# Main_SCH.net
KiCad netlist of a schematic drawn in Altium Designer
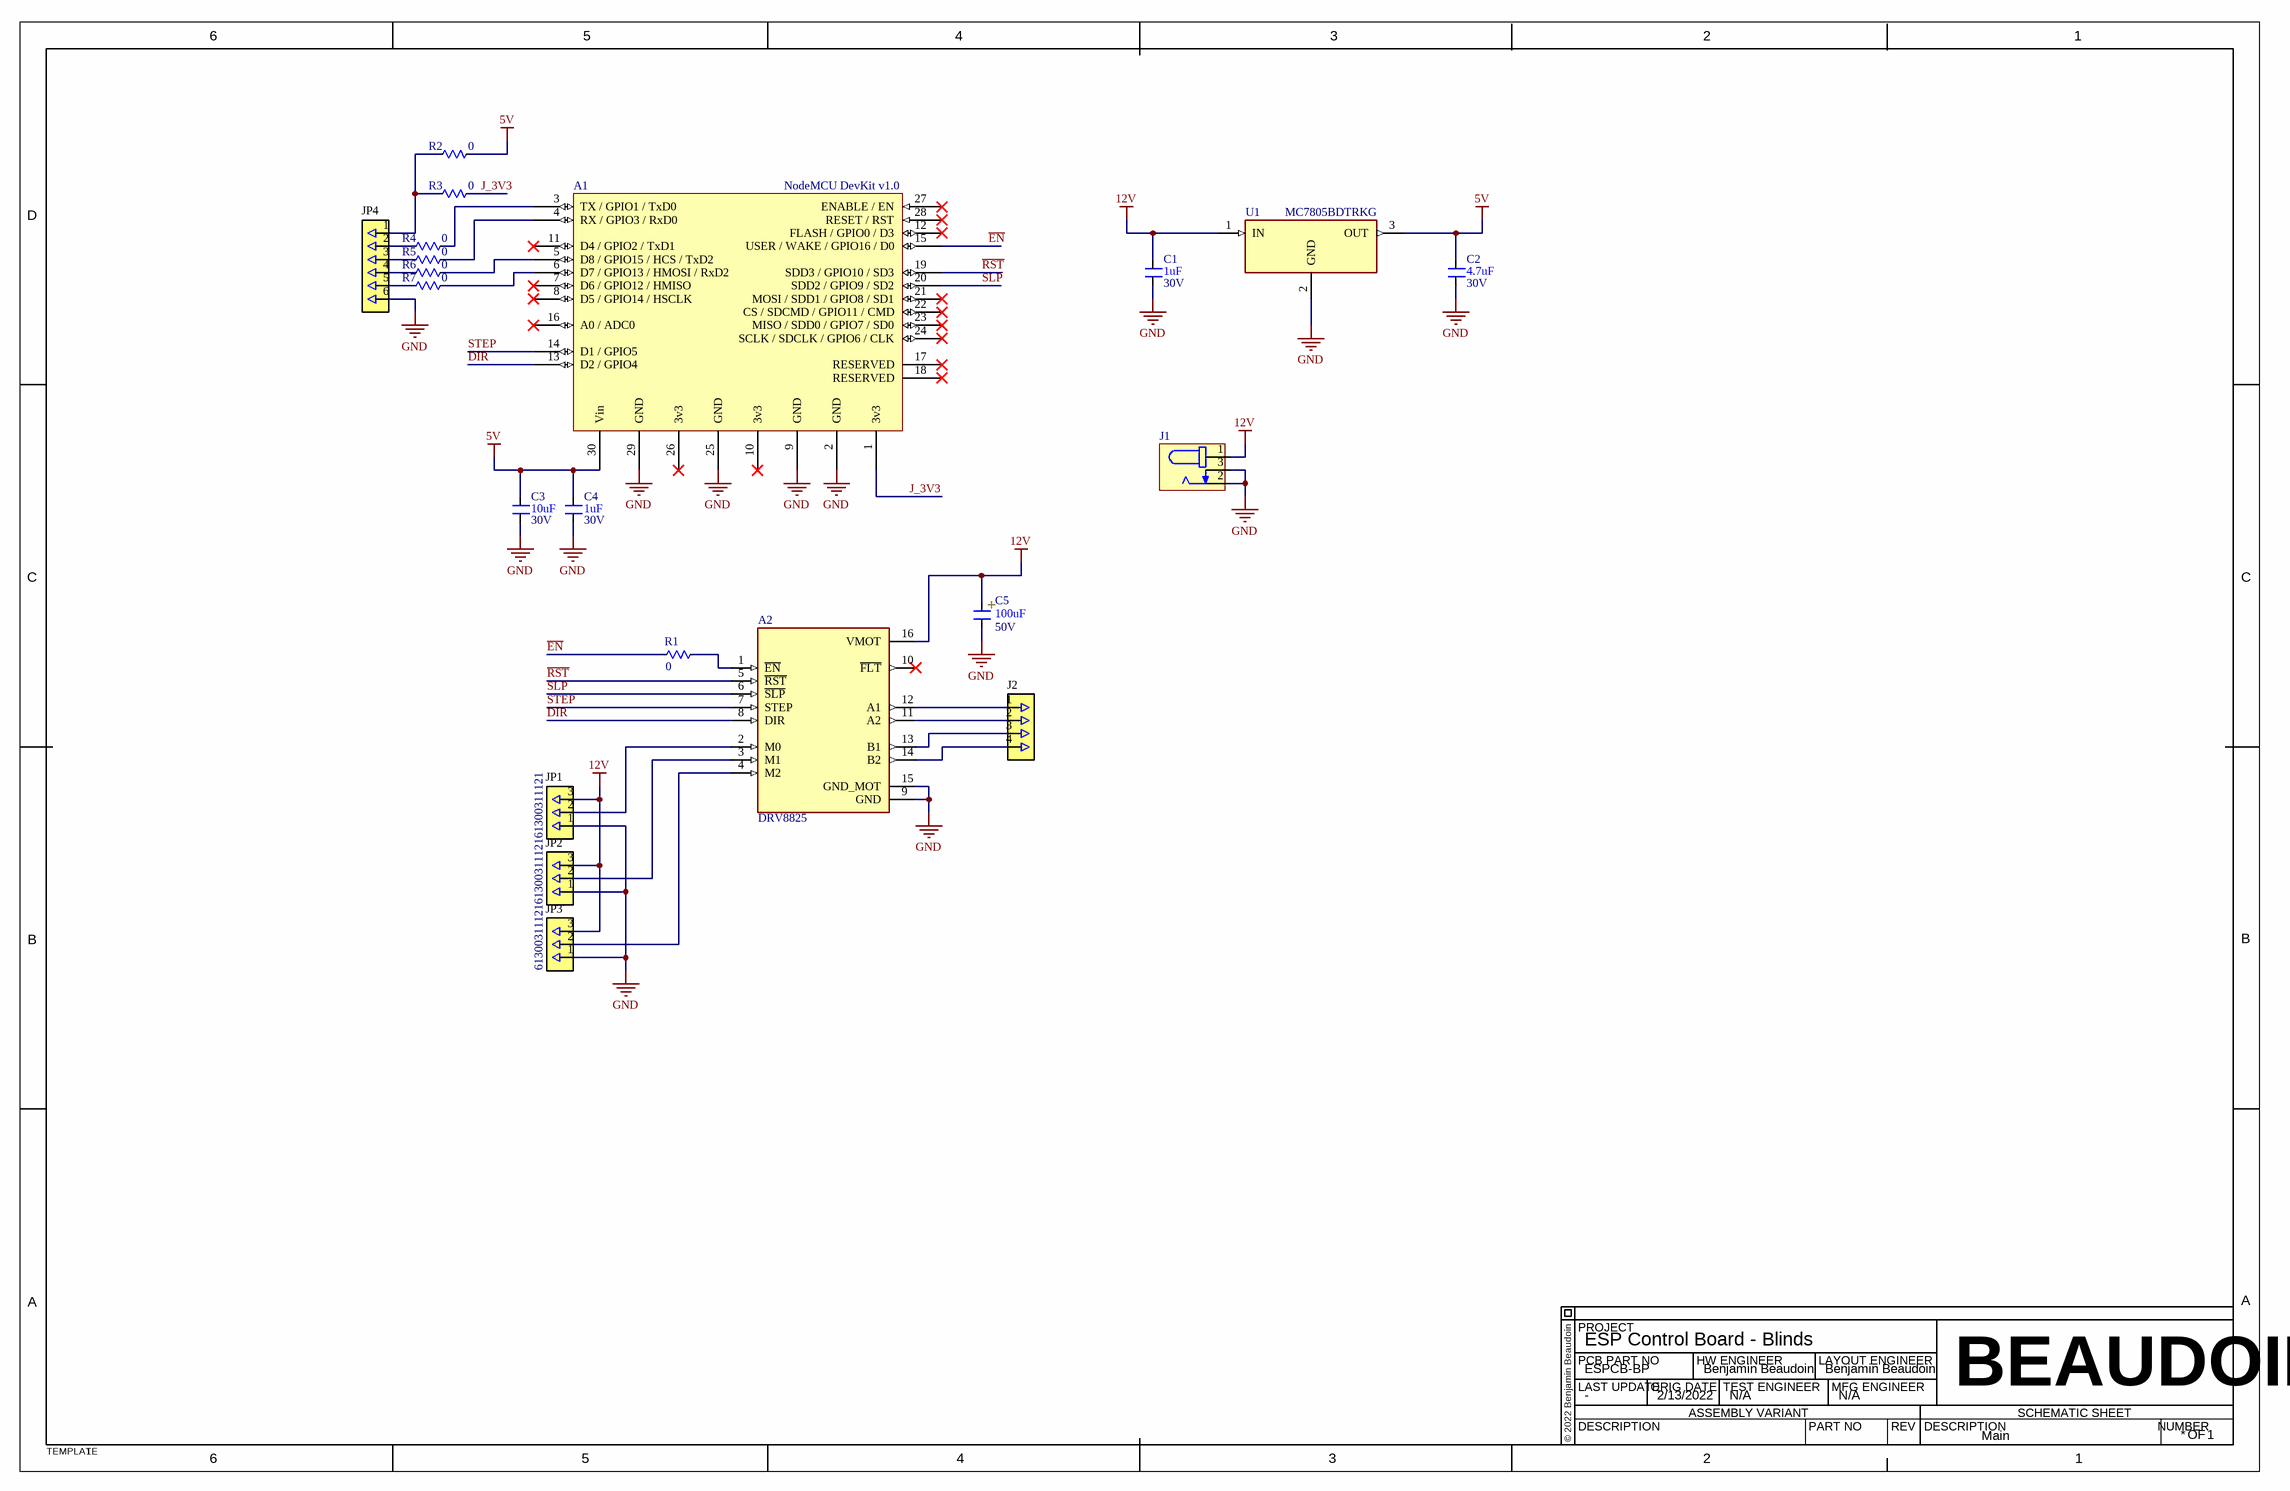
[diagram p0: Main_SCH.SchDoc]

(export (version "E")
  (design (tool "Eeschema 10.0.6"))
  (components
    (comp (ref "A1")
      (value "NodeMCU DevKit v1.0")
      (footprint "NodeMCU DevKit v1.0 - No Labels")
      (libsource (lib "Motorized_Blinds_IntLib") (part "NodeMCU DevKit v1.0"))
    )
    (comp (ref "A2")
      (value "DRV8825")
      (footprint "IC_DRV8825_STEPPER_MOTOR_DRIVER_CARRIER")
      (description "DRV8825 Motor Controller/Driver Power Management Evaluation Board")
      (fields (field (name "MANUFACTURER") "Pololu"))
      (libsource (lib "Motorized_Blinds_IntLib") (part "DRV8825_STEPPER_MOTOR_DRIVER_CARRIER"))
    )
    (comp (ref "C1")
      (value "1uF")
      (footprint "C0603")
      (description "SMCAP NoPol")
      (fields (field (name "VMAX") "30V"))
      (libsource (lib "Motorized_Blinds_IntLib") (part "CAP-NoPol"))
    )
    (comp (ref "C2")
      (value "4.7uF")
      (footprint "C0603")
      (description "SMCAP NoPol")
      (fields (field (name "VMAX") "30V"))
      (libsource (lib "Motorized_Blinds_IntLib") (part "CAP-NoPol"))
    )
    (comp (ref "C3")
      (value "10uF")
      (footprint "C0805")
      (description "SMCAP NoPol")
      (fields (field (name "VMAX") "30V"))
      (libsource (lib "Motorized_Blinds_IntLib") (part "CAP-NoPol"))
    )
    (comp (ref "C4")
      (value "1uF")
      (footprint "C0603")
      (description "SMCAP NoPol")
      (fields (field (name "VMAX") "30V"))
      (libsource (lib "Motorized_Blinds_IntLib") (part "CAP-NoPol"))
    )
    (comp (ref "C5")
      (value "100uF")
      (footprint "CAPAE1050X1050N")
      (description "CAP ALUM 100UF 20% 50V SMD")
      (fields (field (name "MANUFACTURER") "Vishay") (field (name "VMAX") "50V"))
      (libsource (lib "Motorized_Blinds_IntLib") (part "CAP-Pol_MAL214699103E3"))
    )
    (comp (ref "J1")
      (value "PJ-036AH-SMT-TR")
      (footprint "CUI_PJ-036AH-SMT-TR")
      (description "2.0 x 6.3 mm, 5.0 A, Horizontal, Surface Mount _SMT_, Dc Power Jack Connector")
      (fields (field (name "MANUFACTURER") "CUI Devices"))
      (libsource (lib "Motorized_Blinds_IntLib") (part "PJ-036AH-SMT-TR"))
    )
    (comp (ref "J2")
      (value "~")
      (footprint "JP_J4_2.54mm")
      (description "CONN HEADER VERT 4POS 2.54MM")
      (libsource (lib "Motorized_Blinds_IntLib") (part "JP_J4_2.54mm"))
    )
    (comp (ref "JP1")
      (value "61300311121")
      (footprint "JP_61300311121")
      (description "CONN HEADER VERT 3POS 2.54MM")
      (libsource (lib "Motorized_Blinds_IntLib") (part "JP_61300311121"))
    )
    (comp (ref "JP2")
      (value "61300311121")
      (footprint "JP_61300311121")
      (description "CONN HEADER VERT 3POS 2.54MM")
      (libsource (lib "Motorized_Blinds_IntLib") (part "JP_61300311121"))
    )
    (comp (ref "JP3")
      (value "61300311121")
      (footprint "JP_61300311121")
      (description "CONN HEADER VERT 3POS 2.54MM")
      (libsource (lib "Motorized_Blinds_IntLib") (part "JP_61300311121"))
    )
    (comp (ref "JP4")
      (value "~")
      (footprint "JP_J6_2.54mm")
      (description "CONN HEADER VERT 6POS 2.54MM")
      (libsource (lib "Motorized_Blinds_IntLib") (part "JP_J6_2.54mm"))
    )
    (comp (ref "R1")
      (value "0")
      (footprint "R0603")
      (description "SMRES")
      (libsource (lib "Motorized_Blinds_IntLib") (part "Res"))
    )
    (comp (ref "R2")
      (value "0")
      (footprint "R0603")
      (description "SMRES")
      (libsource (lib "Motorized_Blinds_IntLib") (part "Res"))
    )
    (comp (ref "R3")
      (value "0")
      (footprint "R0603")
      (description "SMRES")
      (libsource (lib "Motorized_Blinds_IntLib") (part "Res"))
    )
    (comp (ref "R4")
      (value "0")
      (footprint "R0603")
      (description "SMRES")
      (libsource (lib "Motorized_Blinds_IntLib") (part "Res"))
    )
    (comp (ref "R5")
      (value "0")
      (footprint "R0603")
      (description "SMRES")
      (libsource (lib "Motorized_Blinds_IntLib") (part "Res"))
    )
    (comp (ref "R6")
      (value "0")
      (footprint "R0603")
      (description "SMRES")
      (libsource (lib "Motorized_Blinds_IntLib") (part "Res"))
    )
    (comp (ref "R7")
      (value "0")
      (footprint "R0603")
      (description "SMRES")
      (libsource (lib "Motorized_Blinds_IntLib") (part "Res"))
    )
    (comp (ref "U1")
      (value "MC7805BDTRKG")
      (footprint "DPAK229P990X238-4N")
      (description "Linear Voltage Regulator IC 1 Output 1A DPAK")
      (fields (field (name "MANUFACTURER") "ON Semiconductor"))
      (libsource (lib "Motorized_Blinds_IntLib") (part "MC7805BDTRKG"))
    )
  )
  (nets
    (net (code "1") (name "/DIR") (class "Default")
      (node (ref "A1") (pin "13") (pinfunction "D2_/_GPIO4_13") (pintype "bidirectional"))
      (node (ref "A2") (pin "8") (pinfunction "DIR_8") (pintype "input"))
    )
    (net (code "2") (name "/J_3V3") (class "Default")
      (node (ref "A1") (pin "1") (pinfunction "3v3_1") (pintype "power_in"))
      (node (ref "R3") (pin "2") (pintype "passive"))
    )
    (net (code "3") (name "/STEP") (class "Default")
      (node (ref "A1") (pin "14") (pinfunction "D1_/_GPIO5_14") (pintype "bidirectional"))
      (node (ref "A2") (pin "7") (pinfunction "STEP_7") (pintype "input"))
    )
    (net (code "4") (name "/~{EN}") (class "Default")
      (node (ref "A1") (pin "15") (pinfunction "USER_/_WAKE_/_GPIO16_/_D0_15") (pintype "bidirectional"))
      (node (ref "R1") (pin "1") (pintype "passive"))
    )
    (net (code "5") (name "/~{RST}") (class "Default")
      (node (ref "A1") (pin "19") (pinfunction "SDD3_/_GPIO10_/_SD3_19") (pintype "bidirectional"))
      (node (ref "A2") (pin "5") (pinfunction "~{RST}_5") (pintype "input"))
    )
    (net (code "6") (name "/~{SLP}") (class "Default")
      (node (ref "A1") (pin "20") (pinfunction "SDD2_/_GPIO9_/_SD2_20") (pintype "bidirectional"))
      (node (ref "A2") (pin "6") (pinfunction "~{SLP}_6") (pintype "input"))
    )
    (net (code "7") (name "5V") (class "Default")
      (node (ref "A1") (pin "30") (pinfunction "Vin_30") (pintype "passive"))
      (node (ref "C2") (pin "1") (pintype "passive"))
      (node (ref "C3") (pin "1") (pintype "passive"))
      (node (ref "C4") (pin "1") (pintype "passive"))
      (node (ref "R2") (pin "2") (pintype "passive"))
      (node (ref "U1") (pin "3") (pinfunction "OUT_3") (pintype "output"))
    )
    (net (code "8") (name "12V") (class "Default")
      (node (ref "A2") (pin "16") (pinfunction "VMOT_16") (pintype "power_in"))
      (node (ref "C1") (pin "1") (pintype "passive"))
      (node (ref "C5") (pin "1") (pintype "passive"))
      (node (ref "J1") (pin "1") (pinfunction "1_1") (pintype "passive"))
      (node (ref "JP1") (pin "3") (pintype "passive"))
      (node (ref "JP2") (pin "3") (pintype "passive"))
      (node (ref "JP3") (pin "3") (pintype "passive"))
      (node (ref "U1") (pin "1") (pinfunction "IN_1") (pintype "input"))
    )
    (net (code "9") (name "GND") (class "Default")
      (node (ref "A1") (pin "2") (pinfunction "GND_2") (pintype "power_in"))
      (node (ref "A1") (pin "25") (pinfunction "GND_25") (pintype "power_in"))
      (node (ref "A1") (pin "29") (pinfunction "GND_29") (pintype "passive"))
      (node (ref "A1") (pin "9") (pinfunction "GND_9") (pintype "power_in"))
      (node (ref "A2") (pin "15") (pinfunction "GND_MOT_15") (pintype "power_in"))
      (node (ref "A2") (pin "9") (pinfunction "GND_9") (pintype "power_in"))
      (node (ref "C1") (pin "2") (pintype "passive"))
      (node (ref "C2") (pin "2") (pintype "passive"))
      (node (ref "C3") (pin "2") (pintype "passive"))
      (node (ref "C4") (pin "2") (pintype "passive"))
      (node (ref "C5") (pin "2") (pintype "passive"))
      (node (ref "J1") (pin "2") (pinfunction "2_2") (pintype "passive"))
      (node (ref "J1") (pin "3") (pinfunction "3_3") (pintype "passive"))
      (node (ref "JP1") (pin "1") (pintype "passive"))
      (node (ref "JP2") (pin "1") (pintype "passive"))
      (node (ref "JP3") (pin "1") (pintype "passive"))
      (node (ref "JP4") (pin "6") (pintype "passive"))
      (node (ref "U1") (pin "2") (pinfunction "GND_2") (pintype "power_in"))
    )
    (net (code "10") (name "Net-(A1-D7_{slash}_GPIO13_{slash}_HMOSI_{slash}_RxD2)") (class "Default")
      (node (ref "A1") (pin "6") (pinfunction "D7_/_GPIO13_/_HMOSI_/_RxD2_6") (pintype "bidirectional"))
      (node (ref "R7") (pin "2") (pintype "passive"))
    )
    (net (code "11") (name "Net-(A1-D8_{slash}_GPIO15_{slash}_HCS_{slash}_TxD2)") (class "Default")
      (node (ref "A1") (pin "5") (pinfunction "D8_/_GPIO15_/_HCS_/_TxD2_5") (pintype "bidirectional"))
      (node (ref "R6") (pin "2") (pintype "passive"))
    )
    (net (code "12") (name "Net-(A1-RX_{slash}_GPIO3_{slash}_RxD0)") (class "Default")
      (node (ref "A1") (pin "4") (pinfunction "RX_/_GPIO3_/_RxD0_4") (pintype "bidirectional"))
      (node (ref "R5") (pin "2") (pintype "passive"))
    )
    (net (code "13") (name "Net-(A1-TX_{slash}_GPIO1_{slash}_TxD0)") (class "Default")
      (node (ref "A1") (pin "3") (pinfunction "TX_/_GPIO1_/_TxD0_3") (pintype "bidirectional"))
      (node (ref "R4") (pin "2") (pintype "passive"))
    )
    (net (code "14") (name "Net-(A2-A1)") (class "Default")
      (node (ref "A2") (pin "12") (pinfunction "A1_12") (pintype "output"))
      (node (ref "J2") (pin "1") (pintype "passive"))
    )
    (net (code "15") (name "Net-(A2-A2)") (class "Default")
      (node (ref "A2") (pin "11") (pinfunction "A2_11") (pintype "output"))
      (node (ref "J2") (pin "2") (pintype "passive"))
    )
    (net (code "16") (name "Net-(A2-B1)") (class "Default")
      (node (ref "A2") (pin "13") (pinfunction "B1_13") (pintype "output"))
      (node (ref "J2") (pin "3") (pintype "passive"))
    )
    (net (code "17") (name "Net-(A2-B2)") (class "Default")
      (node (ref "A2") (pin "14") (pinfunction "B2_14") (pintype "output"))
      (node (ref "J2") (pin "4") (pintype "passive"))
    )
    (net (code "18") (name "Net-(A2-M0)") (class "Default")
      (node (ref "A2") (pin "2") (pinfunction "M0_2") (pintype "input"))
      (node (ref "JP1") (pin "2") (pintype "passive"))
    )
    (net (code "19") (name "Net-(A2-M1)") (class "Default")
      (node (ref "A2") (pin "3") (pinfunction "M1_3") (pintype "input"))
      (node (ref "JP2") (pin "2") (pintype "passive"))
    )
    (net (code "20") (name "Net-(A2-M2)") (class "Default")
      (node (ref "A2") (pin "4") (pinfunction "M2_4") (pintype "input"))
      (node (ref "JP3") (pin "2") (pintype "passive"))
    )
    (net (code "21") (name "Net-(A2-~{EN})") (class "Default")
      (node (ref "A2") (pin "1") (pinfunction "~{EN}_1") (pintype "input"))
      (node (ref "R1") (pin "2") (pintype "passive"))
    )
    (net (code "22") (name "Net-(JP4-Pad1)") (class "Default")
      (node (ref "JP4") (pin "1") (pintype "passive"))
      (node (ref "R2") (pin "1") (pintype "passive"))
      (node (ref "R3") (pin "1") (pintype "passive"))
    )
    (net (code "23") (name "Net-(JP4-Pad2)") (class "Default")
      (node (ref "JP4") (pin "2") (pintype "passive"))
      (node (ref "R4") (pin "1") (pintype "passive"))
    )
    (net (code "24") (name "Net-(JP4-Pad3)") (class "Default")
      (node (ref "JP4") (pin "3") (pintype "passive"))
      (node (ref "R5") (pin "1") (pintype "passive"))
    )
    (net (code "25") (name "Net-(JP4-Pad4)") (class "Default")
      (node (ref "JP4") (pin "4") (pintype "passive"))
      (node (ref "R6") (pin "1") (pintype "passive"))
    )
    (net (code "26") (name "Net-(JP4-Pad5)") (class "Default")
      (node (ref "JP4") (pin "5") (pintype "passive"))
      (node (ref "R7") (pin "1") (pintype "passive"))
    )
    (net (code "27") (name "unconnected-(A1-3v3-Pad10)") (class "Default")
      (node (ref "A1") (pin "10") (pinfunction "3v3_10") (pintype "power_in+no_connect"))
    )
    (net (code "28") (name "unconnected-(A1-3v3-Pad26)") (class "Default")
      (node (ref "A1") (pin "26") (pinfunction "3v3_26") (pintype "power_in+no_connect"))
    )
    (net (code "29") (name "unconnected-(A1-A0_{slash}_ADC0-Pad16)") (class "Default")
      (node (ref "A1") (pin "16") (pinfunction "A0_/_ADC0_16") (pintype "bidirectional+no_connect"))
    )
    (net (code "30") (name "unconnected-(A1-CS_{slash}_SDCMD_{slash}_GPIO11_{slash}_CMD-Pad22)") (class "Default")
      (node (ref "A1") (pin "22") (pinfunction "CS_/_SDCMD_/_GPIO11_/_CMD_22") (pintype "bidirectional+no_connect"))
    )
    (net (code "31") (name "unconnected-(A1-D4_{slash}_GPIO2_{slash}_TxD1-Pad11)") (class "Default")
      (node (ref "A1") (pin "11") (pinfunction "D4_/_GPIO2_/_TxD1_11") (pintype "bidirectional+no_connect"))
    )
    (net (code "32") (name "unconnected-(A1-D5_{slash}_GPIO14_{slash}_HSCLK-Pad8)") (class "Default")
      (node (ref "A1") (pin "8") (pinfunction "D5_/_GPIO14_/_HSCLK_8") (pintype "bidirectional+no_connect"))
    )
    (net (code "33") (name "unconnected-(A1-D6_{slash}_GPIO12_{slash}_HMISO-Pad7)") (class "Default")
      (node (ref "A1") (pin "7") (pinfunction "D6_/_GPIO12_/_HMISO_7") (pintype "bidirectional+no_connect"))
    )
    (net (code "34") (name "unconnected-(A1-ENABLE_{slash}_EN-Pad27)") (class "Default")
      (node (ref "A1") (pin "27") (pinfunction "ENABLE_/_EN_27") (pintype "input+no_connect"))
    )
    (net (code "35") (name "unconnected-(A1-FLASH_{slash}_GPIO0_{slash}_D3-Pad12)") (class "Default")
      (node (ref "A1") (pin "12") (pinfunction "FLASH_/_GPIO0_/_D3_12") (pintype "bidirectional+no_connect"))
    )
    (net (code "36") (name "unconnected-(A1-MISO_{slash}_SDD0_{slash}_GPIO7_{slash}_SD0-Pad23)") (class "Default")
      (node (ref "A1") (pin "23") (pinfunction "MISO_/_SDD0_/_GPIO7_/_SD0_23") (pintype "bidirectional+no_connect"))
    )
    (net (code "37") (name "unconnected-(A1-MOSI_{slash}_SDD1_{slash}_GPIO8_{slash}_SD1-Pad21)") (class "Default")
      (node (ref "A1") (pin "21") (pinfunction "MOSI_/_SDD1_/_GPIO8_/_SD1_21") (pintype "bidirectional+no_connect"))
    )
    (net (code "38") (name "unconnected-(A1-RESERVED-Pad17)") (class "Default")
      (node (ref "A1") (pin "17") (pinfunction "RESERVED_17") (pintype "passive+no_connect"))
    )
    (net (code "39") (name "unconnected-(A1-RESERVED-Pad18)") (class "Default")
      (node (ref "A1") (pin "18") (pinfunction "RESERVED_18") (pintype "passive+no_connect"))
    )
    (net (code "40") (name "unconnected-(A1-RESET_{slash}_RST-Pad28)") (class "Default")
      (node (ref "A1") (pin "28") (pinfunction "RESET_/_RST_28") (pintype "input+no_connect"))
    )
    (net (code "41") (name "unconnected-(A1-SCLK_{slash}_SDCLK_{slash}_GPIO6_{slash}_CLK-Pad24)") (class "Default")
      (node (ref "A1") (pin "24") (pinfunction "SCLK_/_SDCLK_/_GPIO6_/_CLK_24") (pintype "bidirectional+no_connect"))
    )
    (net (code "42") (name "unconnected-(A2-~{FLT}-Pad10)") (class "Default")
      (node (ref "A2") (pin "10") (pinfunction "~{FLT}_10") (pintype "output+no_connect"))
    )
  )
)
